# button_2LED_parallel.net
KiCad netlist of a schematic drawn in EAGLE
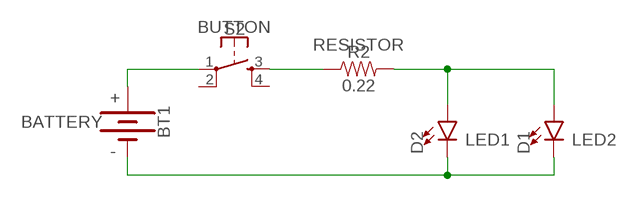
[diagram p0: schematic, sheet 1]

(export (version "E")
  (design (tool "Eeschema 10.0.6"))
  (components
    (comp (ref "BT1")
      (value "BATTERY-9V")
      (footprint "eagle-import:BATTCON_9V")
      (libsource (lib "eagle-import") (part "BATTERY-9V"))
    )
    (comp (ref "D1")
      (value "LED5MM")
      (footprint "eagle-import:LED_5MM")
      (libsource (lib "eagle-import") (part "LED5MM"))
    )
    (comp (ref "D2")
      (value "LED5MM")
      (footprint "eagle-import:LED_5MM")
      (libsource (lib "eagle-import") (part "LED5MM"))
    )
    (comp (ref "R2")
      (value "0.22")
      (footprint "eagle-import:0805")
      (libsource (lib "eagle-import") (part "0.22OHM-0805-1/4W-1%"))
    )
    (comp (ref "S2")
      (value "MOMENTARY-SWITCH-SPST-2-SMD-4.6X2.8MM")
      (footprint "eagle-import:TACTILE_SWITCH_SMD_4.6X2.8MM")
      (libsource (lib "eagle-import") (part "MOMENTARY-SWITCH-SPST-2-SMD-4.6X2.8MM"))
    )
  )
  (nets
    (net (code "1") (name "Net-(BT1-Pad+)") (class "Default")
      (node (ref "BT1") (pin "+") (pinfunction "+_+") (pintype "power_in"))
      (node (ref "S2") (pin "1") (pinfunction "1_1") (pintype "passive"))
    )
    (net (code "2") (name "Net-(D1-C)") (class "Default")
      (node (ref "BT1") (pin "-") (pinfunction "-_-") (pintype "power_in"))
      (node (ref "D1") (pin "K") (pinfunction "C_K") (pintype "passive"))
      (node (ref "D2") (pin "K") (pinfunction "C_K") (pintype "passive"))
    )
    (net (code "3") (name "Net-(D1-PadA)") (class "Default")
      (node (ref "D1") (pin "A") (pinfunction "A_A") (pintype "passive"))
      (node (ref "D2") (pin "A") (pinfunction "A_A") (pintype "passive"))
      (node (ref "R2") (pin "2") (pinfunction "2_2") (pintype "passive"))
    )
    (net (code "4") (name "Net-(R2-Pad1)") (class "Default")
      (node (ref "R2") (pin "1") (pinfunction "1_1") (pintype "passive"))
      (node (ref "S2") (pin "3") (pinfunction "3_3") (pintype "passive"))
    )
    (net (code "5") (name "unconnected-(S2-Pad2)") (class "Default")
      (node (ref "S2") (pin "2") (pinfunction "2_2") (pintype "passive"))
    )
    (net (code "6") (name "unconnected-(S2-Pad4)") (class "Default")
      (node (ref "S2") (pin "4") (pinfunction "4_4") (pintype "passive"))
    )
  )
)
